# Output_block.net
KiCad netlist of a schematic drawn in Altium Designer
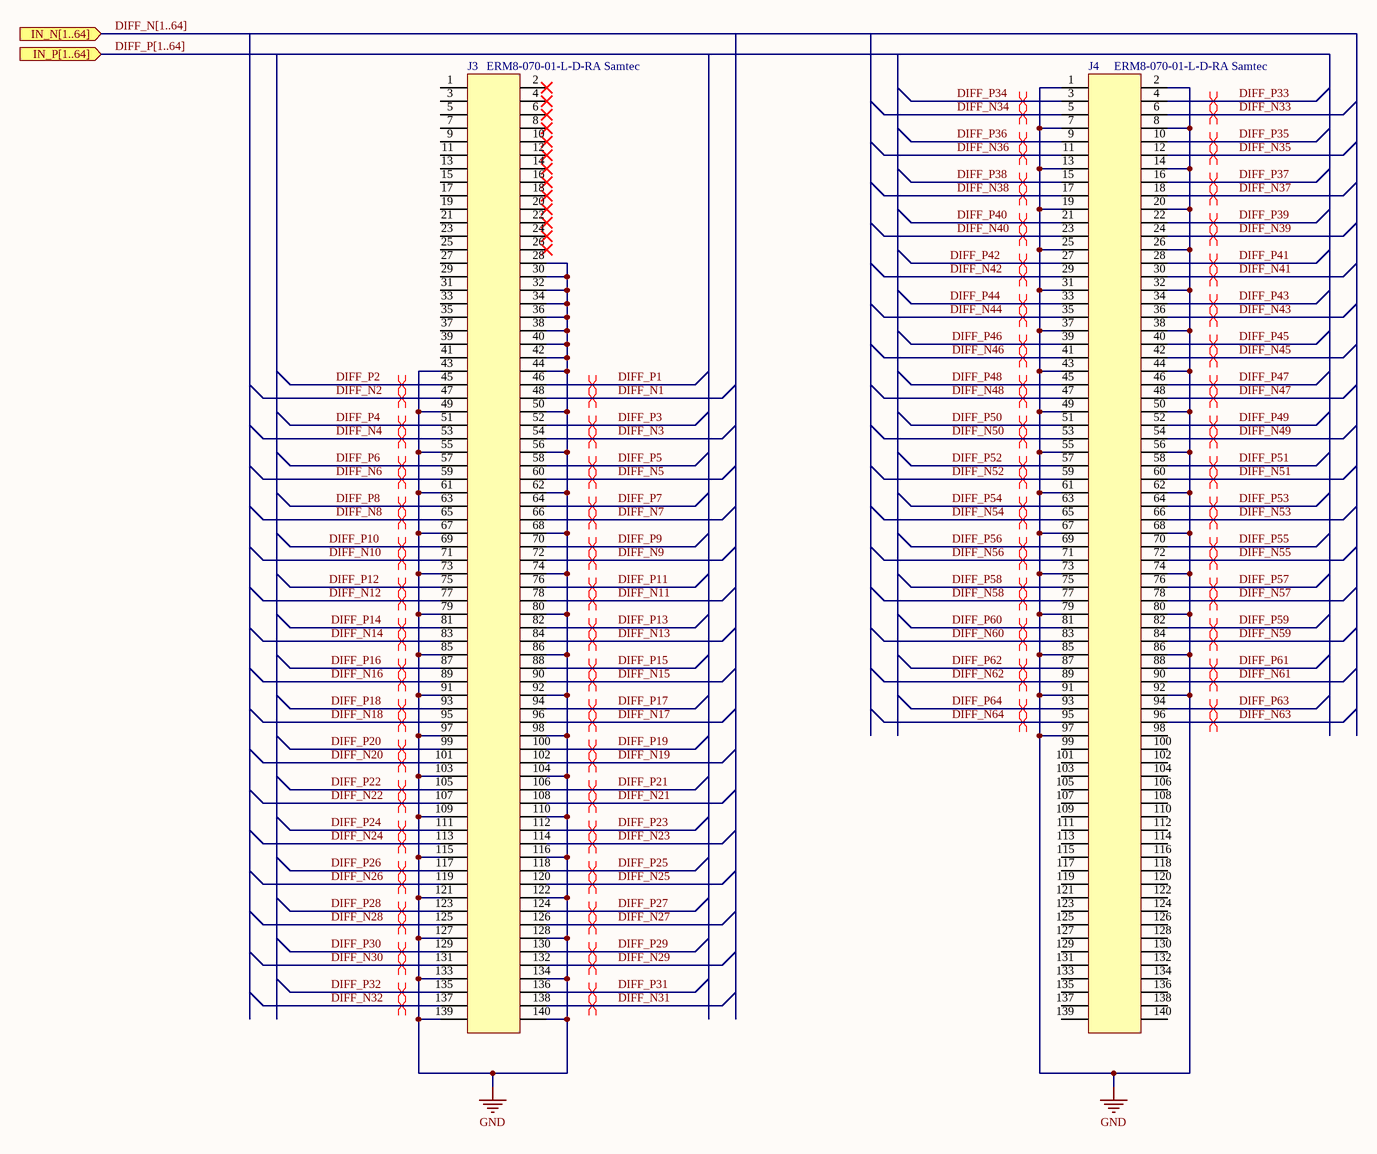
[diagram p0: Output_block.SchDoc]

(export (version "E")
  (design (tool "Eeschema 10.0.6"))
  (components
    (comp (ref "J3")
      (value "ERM8-070-01-L-D-RA Samtec")
      (footprint "ERM8-070-01-L-D-RA")
      (fields (field (name "MANUFACTURER") "Samtec"))
      (libsource (lib "Additional") (part "ERM8-070-01-L-D-RA"))
    )
    (comp (ref "J4")
      (value "ERM8-070-01-L-D-RA Samtec")
      (footprint "ERM8-070-01-L-D-RA")
      (fields (field (name "MANUFACTURER") "Samtec"))
      (libsource (lib "Additional") (part "ERM8-070-01-L-D-RA"))
    )
  )
  (nets
    (net (code "1") (name "/DIFF_N1") (class "Default") (node (ref "J3") (pin "48") (pintype "passive")))
    (net (code "2") (name "/DIFF_N2") (class "Default") (node (ref "J3") (pin "47") (pintype "passive")))
    (net (code "3") (name "/DIFF_N3") (class "Default") (node (ref "J3") (pin "54") (pintype "passive")))
    (net (code "4") (name "/DIFF_N4") (class "Default") (node (ref "J3") (pin "53") (pintype "passive")))
    (net (code "5") (name "/DIFF_N5") (class "Default") (node (ref "J3") (pin "60") (pintype "passive")))
    (net (code "6") (name "/DIFF_N6") (class "Default") (node (ref "J3") (pin "59") (pintype "passive")))
    (net (code "7") (name "/DIFF_N7") (class "Default") (node (ref "J3") (pin "66") (pintype "passive")))
    (net (code "8") (name "/DIFF_N8") (class "Default") (node (ref "J3") (pin "65") (pintype "passive")))
    (net (code "9") (name "/DIFF_N9") (class "Default") (node (ref "J3") (pin "72") (pintype "passive")))
    (net (code "10") (name "/DIFF_N10") (class "Default") (node (ref "J3") (pin "71") (pintype "passive")))
    (net (code "11") (name "/DIFF_N11") (class "Default") (node (ref "J3") (pin "78") (pintype "passive")))
    (net (code "12") (name "/DIFF_N12") (class "Default") (node (ref "J3") (pin "77") (pintype "passive")))
    (net (code "13") (name "/DIFF_N13") (class "Default") (node (ref "J3") (pin "84") (pintype "passive")))
    (net (code "14") (name "/DIFF_N14") (class "Default") (node (ref "J3") (pin "83") (pintype "passive")))
    (net (code "15") (name "/DIFF_N15") (class "Default") (node (ref "J3") (pin "90") (pintype "passive")))
    (net (code "16") (name "/DIFF_N16") (class "Default") (node (ref "J3") (pin "89") (pintype "passive")))
    (net (code "17") (name "/DIFF_N17") (class "Default") (node (ref "J3") (pin "96") (pintype "passive")))
    (net (code "18") (name "/DIFF_N18") (class "Default") (node (ref "J3") (pin "95") (pintype "passive")))
    (net (code "19") (name "/DIFF_N19") (class "Default") (node (ref "J3") (pin "102") (pintype "passive")))
    (net (code "20") (name "/DIFF_N20") (class "Default") (node (ref "J3") (pin "101") (pintype "passive")))
    (net (code "21") (name "/DIFF_N21") (class "Default") (node (ref "J3") (pin "108") (pintype "passive")))
    (net (code "22") (name "/DIFF_N22") (class "Default") (node (ref "J3") (pin "107") (pintype "passive")))
    (net (code "23") (name "/DIFF_N23") (class "Default") (node (ref "J3") (pin "114") (pintype "passive")))
    (net (code "24") (name "/DIFF_N24") (class "Default") (node (ref "J3") (pin "113") (pintype "passive")))
    (net (code "25") (name "/DIFF_N25") (class "Default") (node (ref "J3") (pin "120") (pintype "passive")))
    (net (code "26") (name "/DIFF_N26") (class "Default") (node (ref "J3") (pin "119") (pintype "passive")))
    (net (code "27") (name "/DIFF_N27") (class "Default") (node (ref "J3") (pin "126") (pintype "passive")))
    (net (code "28") (name "/DIFF_N28") (class "Default") (node (ref "J3") (pin "125") (pintype "passive")))
    (net (code "29") (name "/DIFF_N29") (class "Default") (node (ref "J3") (pin "132") (pintype "passive")))
    (net (code "30") (name "/DIFF_N30") (class "Default") (node (ref "J3") (pin "131") (pintype "passive")))
    (net (code "31") (name "/DIFF_N31") (class "Default") (node (ref "J3") (pin "138") (pintype "passive")))
    (net (code "32") (name "/DIFF_N32") (class "Default") (node (ref "J3") (pin "137") (pintype "passive")))
    (net (code "33") (name "/DIFF_N33") (class "Default") (node (ref "J4") (pin "6") (pintype "passive")))
    (net (code "34") (name "/DIFF_N34") (class "Default") (node (ref "J4") (pin "5") (pintype "passive")))
    (net (code "35") (name "/DIFF_N35") (class "Default") (node (ref "J4") (pin "12") (pintype "passive")))
    (net (code "36") (name "/DIFF_N36") (class "Default") (node (ref "J4") (pin "11") (pintype "passive")))
    (net (code "37") (name "/DIFF_N37") (class "Default") (node (ref "J4") (pin "18") (pintype "passive")))
    (net (code "38") (name "/DIFF_N38") (class "Default") (node (ref "J4") (pin "17") (pintype "passive")))
    (net (code "39") (name "/DIFF_N39") (class "Default") (node (ref "J4") (pin "24") (pintype "passive")))
    (net (code "40") (name "/DIFF_N40") (class "Default") (node (ref "J4") (pin "23") (pintype "passive")))
    (net (code "41") (name "/DIFF_N41") (class "Default") (node (ref "J4") (pin "30") (pintype "passive")))
    (net (code "42") (name "/DIFF_N42") (class "Default") (node (ref "J4") (pin "29") (pintype "passive")))
    (net (code "43") (name "/DIFF_N43") (class "Default") (node (ref "J4") (pin "36") (pintype "passive")))
    (net (code "44") (name "/DIFF_N44") (class "Default") (node (ref "J4") (pin "35") (pintype "passive")))
    (net (code "45") (name "/DIFF_N45") (class "Default") (node (ref "J4") (pin "42") (pintype "passive")))
    (net (code "46") (name "/DIFF_N46") (class "Default") (node (ref "J4") (pin "41") (pintype "passive")))
    (net (code "47") (name "/DIFF_N47") (class "Default") (node (ref "J4") (pin "48") (pintype "passive")))
    (net (code "48") (name "/DIFF_N48") (class "Default") (node (ref "J4") (pin "47") (pintype "passive")))
    (net (code "49") (name "/DIFF_N49") (class "Default") (node (ref "J4") (pin "54") (pintype "passive")))
    (net (code "50") (name "/DIFF_N50") (class "Default") (node (ref "J4") (pin "53") (pintype "passive")))
    (net (code "51") (name "/DIFF_N51") (class "Default") (node (ref "J4") (pin "60") (pintype "passive")))
    (net (code "52") (name "/DIFF_N52") (class "Default") (node (ref "J4") (pin "59") (pintype "passive")))
    (net (code "53") (name "/DIFF_N53") (class "Default") (node (ref "J4") (pin "66") (pintype "passive")))
    (net (code "54") (name "/DIFF_N54") (class "Default") (node (ref "J4") (pin "65") (pintype "passive")))
    (net (code "55") (name "/DIFF_N55") (class "Default") (node (ref "J4") (pin "72") (pintype "passive")))
    (net (code "56") (name "/DIFF_N56") (class "Default") (node (ref "J4") (pin "71") (pintype "passive")))
    (net (code "57") (name "/DIFF_N57") (class "Default") (node (ref "J4") (pin "78") (pintype "passive")))
    (net (code "58") (name "/DIFF_N58") (class "Default") (node (ref "J4") (pin "77") (pintype "passive")))
    (net (code "59") (name "/DIFF_N59") (class "Default") (node (ref "J4") (pin "84") (pintype "passive")))
    (net (code "60") (name "/DIFF_N60") (class "Default") (node (ref "J4") (pin "83") (pintype "passive")))
    (net (code "61") (name "/DIFF_N61") (class "Default") (node (ref "J4") (pin "90") (pintype "passive")))
    (net (code "62") (name "/DIFF_N62") (class "Default") (node (ref "J4") (pin "89") (pintype "passive")))
    (net (code "63") (name "/DIFF_N63") (class "Default") (node (ref "J4") (pin "96") (pintype "passive")))
    (net (code "64") (name "/DIFF_N64") (class "Default") (node (ref "J4") (pin "95") (pintype "passive")))
    (net (code "66") (name "/DIFF_P1") (class "Default") (node (ref "J3") (pin "46") (pintype "passive")))
    (net (code "67") (name "/DIFF_P2") (class "Default") (node (ref "J3") (pin "45") (pintype "passive")))
    (net (code "68") (name "/DIFF_P3") (class "Default") (node (ref "J3") (pin "52") (pintype "passive")))
    (net (code "69") (name "/DIFF_P4") (class "Default") (node (ref "J3") (pin "51") (pintype "passive")))
    (net (code "70") (name "/DIFF_P5") (class "Default") (node (ref "J3") (pin "58") (pintype "passive")))
    (net (code "71") (name "/DIFF_P6") (class "Default") (node (ref "J3") (pin "57") (pintype "passive")))
    (net (code "72") (name "/DIFF_P7") (class "Default") (node (ref "J3") (pin "64") (pintype "passive")))
    (net (code "73") (name "/DIFF_P8") (class "Default") (node (ref "J3") (pin "63") (pintype "passive")))
    (net (code "74") (name "/DIFF_P9") (class "Default") (node (ref "J3") (pin "70") (pintype "passive")))
    (net (code "75") (name "/DIFF_P10") (class "Default") (node (ref "J3") (pin "69") (pintype "passive")))
    (net (code "76") (name "/DIFF_P11") (class "Default") (node (ref "J3") (pin "76") (pintype "passive")))
    (net (code "77") (name "/DIFF_P12") (class "Default") (node (ref "J3") (pin "75") (pintype "passive")))
    (net (code "78") (name "/DIFF_P13") (class "Default") (node (ref "J3") (pin "82") (pintype "passive")))
    (net (code "79") (name "/DIFF_P14") (class "Default") (node (ref "J3") (pin "81") (pintype "passive")))
    (net (code "80") (name "/DIFF_P15") (class "Default") (node (ref "J3") (pin "88") (pintype "passive")))
    (net (code "81") (name "/DIFF_P16") (class "Default") (node (ref "J3") (pin "87") (pintype "passive")))
    (net (code "82") (name "/DIFF_P17") (class "Default") (node (ref "J3") (pin "94") (pintype "passive")))
    (net (code "83") (name "/DIFF_P18") (class "Default") (node (ref "J3") (pin "93") (pintype "passive")))
    (net (code "84") (name "/DIFF_P19") (class "Default") (node (ref "J3") (pin "100") (pintype "passive")))
    (net (code "85") (name "/DIFF_P20") (class "Default") (node (ref "J3") (pin "99") (pintype "passive")))
    (net (code "86") (name "/DIFF_P21") (class "Default") (node (ref "J3") (pin "106") (pintype "passive")))
    (net (code "87") (name "/DIFF_P22") (class "Default") (node (ref "J3") (pin "105") (pintype "passive")))
    (net (code "88") (name "/DIFF_P23") (class "Default") (node (ref "J3") (pin "112") (pintype "passive")))
    (net (code "89") (name "/DIFF_P24") (class "Default") (node (ref "J3") (pin "111") (pintype "passive")))
    (net (code "90") (name "/DIFF_P25") (class "Default") (node (ref "J3") (pin "118") (pintype "passive")))
    (net (code "91") (name "/DIFF_P26") (class "Default") (node (ref "J3") (pin "117") (pintype "passive")))
    (net (code "92") (name "/DIFF_P27") (class "Default") (node (ref "J3") (pin "124") (pintype "passive")))
    (net (code "93") (name "/DIFF_P28") (class "Default") (node (ref "J3") (pin "123") (pintype "passive")))
    (net (code "94") (name "/DIFF_P29") (class "Default") (node (ref "J3") (pin "130") (pintype "passive")))
    (net (code "95") (name "/DIFF_P30") (class "Default") (node (ref "J3") (pin "129") (pintype "passive")))
    (net (code "96") (name "/DIFF_P31") (class "Default") (node (ref "J3") (pin "136") (pintype "passive")))
    (net (code "97") (name "/DIFF_P32") (class "Default") (node (ref "J3") (pin "135") (pintype "passive")))
    (net (code "98") (name "/DIFF_P33") (class "Default") (node (ref "J4") (pin "4") (pintype "passive")))
    (net (code "99") (name "/DIFF_P34") (class "Default") (node (ref "J4") (pin "3") (pintype "passive")))
    (net (code "100") (name "/DIFF_P35") (class "Default") (node (ref "J4") (pin "10") (pintype "passive")))
    (net (code "101") (name "/DIFF_P36") (class "Default") (node (ref "J4") (pin "9") (pintype "passive")))
    (net (code "102") (name "/DIFF_P37") (class "Default") (node (ref "J4") (pin "16") (pintype "passive")))
    (net (code "103") (name "/DIFF_P38") (class "Default") (node (ref "J4") (pin "15") (pintype "passive")))
    (net (code "104") (name "/DIFF_P39") (class "Default") (node (ref "J4") (pin "22") (pintype "passive")))
    (net (code "105") (name "/DIFF_P40") (class "Default") (node (ref "J4") (pin "21") (pintype "passive")))
    (net (code "106") (name "/DIFF_P41") (class "Default") (node (ref "J4") (pin "28") (pintype "passive")))
    (net (code "107") (name "/DIFF_P42") (class "Default") (node (ref "J4") (pin "27") (pintype "passive")))
    (net (code "108") (name "/DIFF_P43") (class "Default") (node (ref "J4") (pin "34") (pintype "passive")))
    (net (code "109") (name "/DIFF_P44") (class "Default") (node (ref "J4") (pin "33") (pintype "passive")))
    (net (code "110") (name "/DIFF_P45") (class "Default") (node (ref "J4") (pin "40") (pintype "passive")))
    (net (code "111") (name "/DIFF_P46") (class "Default") (node (ref "J4") (pin "39") (pintype "passive")))
    (net (code "112") (name "/DIFF_P47") (class "Default") (node (ref "J4") (pin "46") (pintype "passive")))
    (net (code "113") (name "/DIFF_P48") (class "Default") (node (ref "J4") (pin "45") (pintype "passive")))
    (net (code "114") (name "/DIFF_P49") (class "Default") (node (ref "J4") (pin "52") (pintype "passive")))
    (net (code "115") (name "/DIFF_P50") (class "Default") (node (ref "J4") (pin "51") (pintype "passive")))
    (net (code "116") (name "/DIFF_P51") (class "Default") (node (ref "J4") (pin "58") (pintype "passive")))
    (net (code "117") (name "/DIFF_P52") (class "Default") (node (ref "J4") (pin "57") (pintype "passive")))
    (net (code "118") (name "/DIFF_P53") (class "Default") (node (ref "J4") (pin "64") (pintype "passive")))
    (net (code "119") (name "/DIFF_P54") (class "Default") (node (ref "J4") (pin "63") (pintype "passive")))
    (net (code "120") (name "/DIFF_P55") (class "Default") (node (ref "J4") (pin "70") (pintype "passive")))
    (net (code "121") (name "/DIFF_P56") (class "Default") (node (ref "J4") (pin "69") (pintype "passive")))
    (net (code "122") (name "/DIFF_P57") (class "Default") (node (ref "J4") (pin "76") (pintype "passive")))
    (net (code "123") (name "/DIFF_P58") (class "Default") (node (ref "J4") (pin "75") (pintype "passive")))
    (net (code "124") (name "/DIFF_P59") (class "Default") (node (ref "J4") (pin "82") (pintype "passive")))
    (net (code "125") (name "/DIFF_P60") (class "Default") (node (ref "J4") (pin "81") (pintype "passive")))
    (net (code "126") (name "/DIFF_P61") (class "Default") (node (ref "J4") (pin "88") (pintype "passive")))
    (net (code "127") (name "/DIFF_P62") (class "Default") (node (ref "J4") (pin "87") (pintype "passive")))
    (net (code "128") (name "/DIFF_P63") (class "Default") (node (ref "J4") (pin "94") (pintype "passive")))
    (net (code "129") (name "/DIFF_P64") (class "Default") (node (ref "J4") (pin "93") (pintype "passive")))
    (net (code "131") (name "GND") (class "Default")
      (node (ref "J3") (pin "103") (pintype "passive"))
      (node (ref "J3") (pin "104") (pintype "passive"))
      (node (ref "J3") (pin "109") (pintype "passive"))
      (node (ref "J3") (pin "110") (pintype "passive"))
      (node (ref "J3") (pin "115") (pintype "passive"))
      (node (ref "J3") (pin "116") (pintype "passive"))
      (node (ref "J3") (pin "121") (pintype "passive"))
      (node (ref "J3") (pin "122") (pintype "passive"))
      (node (ref "J3") (pin "127") (pintype "passive"))
      (node (ref "J3") (pin "128") (pintype "passive"))
      (node (ref "J3") (pin "133") (pintype "passive"))
      (node (ref "J3") (pin "134") (pintype "passive"))
      (node (ref "J3") (pin "139") (pintype "passive"))
      (node (ref "J3") (pin "140") (pintype "passive"))
      (node (ref "J3") (pin "28") (pintype "passive"))
      (node (ref "J3") (pin "30") (pintype "passive"))
      (node (ref "J3") (pin "32") (pintype "passive"))
      (node (ref "J3") (pin "34") (pintype "passive"))
      (node (ref "J3") (pin "36") (pintype "passive"))
      (node (ref "J3") (pin "38") (pintype "passive"))
      (node (ref "J3") (pin "40") (pintype "passive"))
      (node (ref "J3") (pin "42") (pintype "passive"))
      (node (ref "J3") (pin "43") (pintype "passive"))
      (node (ref "J3") (pin "44") (pintype "passive"))
      (node (ref "J3") (pin "49") (pintype "passive"))
      (node (ref "J3") (pin "50") (pintype "passive"))
      (node (ref "J3") (pin "55") (pintype "passive"))
      (node (ref "J3") (pin "56") (pintype "passive"))
      (node (ref "J3") (pin "61") (pintype "passive"))
      (node (ref "J3") (pin "62") (pintype "passive"))
      (node (ref "J3") (pin "67") (pintype "passive"))
      (node (ref "J3") (pin "68") (pintype "passive"))
      (node (ref "J3") (pin "73") (pintype "passive"))
      (node (ref "J3") (pin "74") (pintype "passive"))
      (node (ref "J3") (pin "79") (pintype "passive"))
      (node (ref "J3") (pin "80") (pintype "passive"))
      (node (ref "J3") (pin "85") (pintype "passive"))
      (node (ref "J3") (pin "86") (pintype "passive"))
      (node (ref "J3") (pin "91") (pintype "passive"))
      (node (ref "J3") (pin "92") (pintype "passive"))
      (node (ref "J3") (pin "97") (pintype "passive"))
      (node (ref "J3") (pin "98") (pintype "passive"))
      (node (ref "J4") (pin "1") (pintype "passive"))
      (node (ref "J4") (pin "13") (pintype "passive"))
      (node (ref "J4") (pin "14") (pintype "passive"))
      (node (ref "J4") (pin "19") (pintype "passive"))
      (node (ref "J4") (pin "2") (pintype "passive"))
      (node (ref "J4") (pin "20") (pintype "passive"))
      (node (ref "J4") (pin "25") (pintype "passive"))
      (node (ref "J4") (pin "26") (pintype "passive"))
      (node (ref "J4") (pin "31") (pintype "passive"))
      (node (ref "J4") (pin "32") (pintype "passive"))
      (node (ref "J4") (pin "37") (pintype "passive"))
      (node (ref "J4") (pin "38") (pintype "passive"))
      (node (ref "J4") (pin "43") (pintype "passive"))
      (node (ref "J4") (pin "44") (pintype "passive"))
      (node (ref "J4") (pin "49") (pintype "passive"))
      (node (ref "J4") (pin "50") (pintype "passive"))
      (node (ref "J4") (pin "55") (pintype "passive"))
      (node (ref "J4") (pin "56") (pintype "passive"))
      (node (ref "J4") (pin "61") (pintype "passive"))
      (node (ref "J4") (pin "62") (pintype "passive"))
      (node (ref "J4") (pin "67") (pintype "passive"))
      (node (ref "J4") (pin "68") (pintype "passive"))
      (node (ref "J4") (pin "7") (pintype "passive"))
      (node (ref "J4") (pin "73") (pintype "passive"))
      (node (ref "J4") (pin "74") (pintype "passive"))
      (node (ref "J4") (pin "79") (pintype "passive"))
      (node (ref "J4") (pin "8") (pintype "passive"))
      (node (ref "J4") (pin "80") (pintype "passive"))
      (node (ref "J4") (pin "85") (pintype "passive"))
      (node (ref "J4") (pin "86") (pintype "passive"))
      (node (ref "J4") (pin "91") (pintype "passive"))
      (node (ref "J4") (pin "92") (pintype "passive"))
      (node (ref "J4") (pin "97") (pintype "passive"))
    )
    (net (code "132") (name "unconnected-(J3-Pad1)") (class "Default")
      (node (ref "J3") (pin "1") (pintype "passive"))
    )
    (net (code "133") (name "unconnected-(J3-Pad2)") (class "Default")
      (node (ref "J3") (pin "2") (pintype "passive+no_connect"))
    )
    (net (code "134") (name "unconnected-(J3-Pad3)") (class "Default")
      (node (ref "J3") (pin "3") (pintype "passive"))
    )
    (net (code "135") (name "unconnected-(J3-Pad4)") (class "Default")
      (node (ref "J3") (pin "4") (pintype "passive+no_connect"))
    )
    (net (code "136") (name "unconnected-(J3-Pad5)") (class "Default")
      (node (ref "J3") (pin "5") (pintype "passive"))
    )
    (net (code "137") (name "unconnected-(J3-Pad6)") (class "Default")
      (node (ref "J3") (pin "6") (pintype "passive+no_connect"))
    )
    (net (code "138") (name "unconnected-(J3-Pad7)") (class "Default")
      (node (ref "J3") (pin "7") (pintype "passive"))
    )
    (net (code "139") (name "unconnected-(J3-Pad8)") (class "Default")
      (node (ref "J3") (pin "8") (pintype "passive+no_connect"))
    )
    (net (code "140") (name "unconnected-(J3-Pad9)") (class "Default")
      (node (ref "J3") (pin "9") (pintype "passive"))
    )
    (net (code "141") (name "unconnected-(J3-Pad10)") (class "Default")
      (node (ref "J3") (pin "10") (pintype "passive+no_connect"))
    )
    (net (code "142") (name "unconnected-(J3-Pad11)") (class "Default")
      (node (ref "J3") (pin "11") (pintype "passive"))
    )
    (net (code "143") (name "unconnected-(J3-Pad12)") (class "Default")
      (node (ref "J3") (pin "12") (pintype "passive+no_connect"))
    )
    (net (code "144") (name "unconnected-(J3-Pad13)") (class "Default")
      (node (ref "J3") (pin "13") (pintype "passive"))
    )
    (net (code "145") (name "unconnected-(J3-Pad14)") (class "Default")
      (node (ref "J3") (pin "14") (pintype "passive+no_connect"))
    )
    (net (code "146") (name "unconnected-(J3-Pad15)") (class "Default")
      (node (ref "J3") (pin "15") (pintype "passive"))
    )
    (net (code "147") (name "unconnected-(J3-Pad16)") (class "Default")
      (node (ref "J3") (pin "16") (pintype "passive+no_connect"))
    )
    (net (code "148") (name "unconnected-(J3-Pad17)") (class "Default")
      (node (ref "J3") (pin "17") (pintype "passive"))
    )
    (net (code "149") (name "unconnected-(J3-Pad18)") (class "Default")
      (node (ref "J3") (pin "18") (pintype "passive+no_connect"))
    )
    (net (code "150") (name "unconnected-(J3-Pad19)") (class "Default")
      (node (ref "J3") (pin "19") (pintype "passive"))
    )
    (net (code "151") (name "unconnected-(J3-Pad20)") (class "Default")
      (node (ref "J3") (pin "20") (pintype "passive+no_connect"))
    )
    (net (code "152") (name "unconnected-(J3-Pad21)") (class "Default")
      (node (ref "J3") (pin "21") (pintype "passive"))
    )
    (net (code "153") (name "unconnected-(J3-Pad22)") (class "Default")
      (node (ref "J3") (pin "22") (pintype "passive+no_connect"))
    )
    (net (code "154") (name "unconnected-(J3-Pad23)") (class "Default")
      (node (ref "J3") (pin "23") (pintype "passive"))
    )
    (net (code "155") (name "unconnected-(J3-Pad24)") (class "Default")
      (node (ref "J3") (pin "24") (pintype "passive+no_connect"))
    )
    (net (code "156") (name "unconnected-(J3-Pad25)") (class "Default")
      (node (ref "J3") (pin "25") (pintype "passive"))
    )
    (net (code "157") (name "unconnected-(J3-Pad26)") (class "Default")
      (node (ref "J3") (pin "26") (pintype "passive+no_connect"))
    )
    (net (code "158") (name "unconnected-(J3-Pad27)") (class "Default")
      (node (ref "J3") (pin "27") (pintype "passive"))
    )
    (net (code "159") (name "unconnected-(J3-Pad29)") (class "Default")
      (node (ref "J3") (pin "29") (pintype "passive"))
    )
    (net (code "160") (name "unconnected-(J3-Pad31)") (class "Default")
      (node (ref "J3") (pin "31") (pintype "passive"))
    )
    (net (code "161") (name "unconnected-(J3-Pad33)") (class "Default")
      (node (ref "J3") (pin "33") (pintype "passive"))
    )
    (net (code "162") (name "unconnected-(J3-Pad35)") (class "Default")
      (node (ref "J3") (pin "35") (pintype "passive"))
    )
    (net (code "163") (name "unconnected-(J3-Pad37)") (class "Default")
      (node (ref "J3") (pin "37") (pintype "passive"))
    )
    (net (code "164") (name "unconnected-(J3-Pad39)") (class "Default")
      (node (ref "J3") (pin "39") (pintype "passive"))
    )
    (net (code "165") (name "unconnected-(J3-Pad41)") (class "Default")
      (node (ref "J3") (pin "41") (pintype "passive"))
    )
    (net (code "166") (name "unconnected-(J4-Pad98)") (class "Default")
      (node (ref "J4") (pin "98") (pintype "passive"))
    )
    (net (code "167") (name "unconnected-(J4-Pad99)") (class "Default")
      (node (ref "J4") (pin "99") (pintype "passive"))
    )
    (net (code "168") (name "unconnected-(J4-Pad100)") (class "Default")
      (node (ref "J4") (pin "100") (pintype "passive"))
    )
    (net (code "169") (name "unconnected-(J4-Pad101)") (class "Default")
      (node (ref "J4") (pin "101") (pintype "passive"))
    )
    (net (code "170") (name "unconnected-(J4-Pad102)") (class "Default")
      (node (ref "J4") (pin "102") (pintype "passive"))
    )
    (net (code "171") (name "unconnected-(J4-Pad103)") (class "Default")
      (node (ref "J4") (pin "103") (pintype "passive"))
    )
    (net (code "172") (name "unconnected-(J4-Pad104)") (class "Default")
      (node (ref "J4") (pin "104") (pintype "passive"))
    )
    (net (code "173") (name "unconnected-(J4-Pad105)") (class "Default")
      (node (ref "J4") (pin "105") (pintype "passive"))
    )
    (net (code "174") (name "unconnected-(J4-Pad106)") (class "Default")
      (node (ref "J4") (pin "106") (pintype "passive"))
    )
    (net (code "175") (name "unconnected-(J4-Pad107)") (class "Default")
      (node (ref "J4") (pin "107") (pintype "passive"))
    )
    (net (code "176") (name "unconnected-(J4-Pad108)") (class "Default")
      (node (ref "J4") (pin "108") (pintype "passive"))
    )
    (net (code "177") (name "unconnected-(J4-Pad109)") (class "Default")
      (node (ref "J4") (pin "109") (pintype "passive"))
    )
    (net (code "178") (name "unconnected-(J4-Pad110)") (class "Default")
      (node (ref "J4") (pin "110") (pintype "passive"))
    )
    (net (code "179") (name "unconnected-(J4-Pad111)") (class "Default")
      (node (ref "J4") (pin "111") (pintype "passive"))
    )
    (net (code "180") (name "unconnected-(J4-Pad112)") (class "Default")
      (node (ref "J4") (pin "112") (pintype "passive"))
    )
    (net (code "181") (name "unconnected-(J4-Pad113)") (class "Default")
      (node (ref "J4") (pin "113") (pintype "passive"))
    )
    (net (code "182") (name "unconnected-(J4-Pad114)") (class "Default")
      (node (ref "J4") (pin "114") (pintype "passive"))
    )
    (net (code "183") (name "unconnected-(J4-Pad115)") (class "Default")
      (node (ref "J4") (pin "115") (pintype "passive"))
    )
    (net (code "184") (name "unconnected-(J4-Pad116)") (class "Default")
      (node (ref "J4") (pin "116") (pintype "passive"))
    )
    (net (code "185") (name "unconnected-(J4-Pad117)") (class "Default")
      (node (ref "J4") (pin "117") (pintype "passive"))
    )
    (net (code "186") (name "unconnected-(J4-Pad118)") (class "Default")
      (node (ref "J4") (pin "118") (pintype "passive"))
    )
    (net (code "187") (name "unconnected-(J4-Pad119)") (class "Default")
      (node (ref "J4") (pin "119") (pintype "passive"))
    )
    (net (code "188") (name "unconnected-(J4-Pad120)") (class "Default")
      (node (ref "J4") (pin "120") (pintype "passive"))
    )
    (net (code "189") (name "unconnected-(J4-Pad121)") (class "Default")
      (node (ref "J4") (pin "121") (pintype "passive"))
    )
    (net (code "190") (name "unconnected-(J4-Pad122)") (class "Default")
      (node (ref "J4") (pin "122") (pintype "passive"))
    )
    (net (code "191") (name "unconnected-(J4-Pad123)") (class "Default")
      (node (ref "J4") (pin "123") (pintype "passive"))
    )
    (net (code "192") (name "unconnected-(J4-Pad124)") (class "Default")
      (node (ref "J4") (pin "124") (pintype "passive"))
    )
    (net (code "193") (name "unconnected-(J4-Pad125)") (class "Default")
      (node (ref "J4") (pin "125") (pintype "passive"))
    )
    (net (code "194") (name "unconnected-(J4-Pad126)") (class "Default")
      (node (ref "J4") (pin "126") (pintype "passive"))
    )
    (net (code "195") (name "unconnected-(J4-Pad127)") (class "Default")
      (node (ref "J4") (pin "127") (pintype "passive"))
    )
    (net (code "196") (name "unconnected-(J4-Pad128)") (class "Default")
      (node (ref "J4") (pin "128") (pintype "passive"))
    )
    (net (code "197") (name "unconnected-(J4-Pad129)") (class "Default")
      (node (ref "J4") (pin "129") (pintype "passive"))
    )
    (net (code "198") (name "unconnected-(J4-Pad130)") (class "Default")
      (node (ref "J4") (pin "130") (pintype "passive"))
    )
    (net (code "199") (name "unconnected-(J4-Pad131)") (class "Default")
      (node (ref "J4") (pin "131") (pintype "passive"))
    )
    (net (code "200") (name "unconnected-(J4-Pad132)") (class "Default")
      (node (ref "J4") (pin "132") (pintype "passive"))
    )
    (net (code "201") (name "unconnected-(J4-Pad133)") (class "Default")
      (node (ref "J4") (pin "133") (pintype "passive"))
    )
    (net (code "202") (name "unconnected-(J4-Pad134)") (class "Default")
      (node (ref "J4") (pin "134") (pintype "passive"))
    )
    (net (code "203") (name "unconnected-(J4-Pad135)") (class "Default")
      (node (ref "J4") (pin "135") (pintype "passive"))
    )
    (net (code "204") (name "unconnected-(J4-Pad136)") (class "Default")
      (node (ref "J4") (pin "136") (pintype "passive"))
    )
    (net (code "205") (name "unconnected-(J4-Pad137)") (class "Default")
      (node (ref "J4") (pin "137") (pintype "passive"))
    )
    (net (code "206") (name "unconnected-(J4-Pad138)") (class "Default")
      (node (ref "J4") (pin "138") (pintype "passive"))
    )
    (net (code "207") (name "unconnected-(J4-Pad139)") (class "Default")
      (node (ref "J4") (pin "139") (pintype "passive"))
    )
    (net (code "208") (name "unconnected-(J4-Pad140)") (class "Default")
      (node (ref "J4") (pin "140") (pintype "passive"))
    )
  )
)
